# Control.net
KiCad netlist of a schematic drawn in Altium Designer
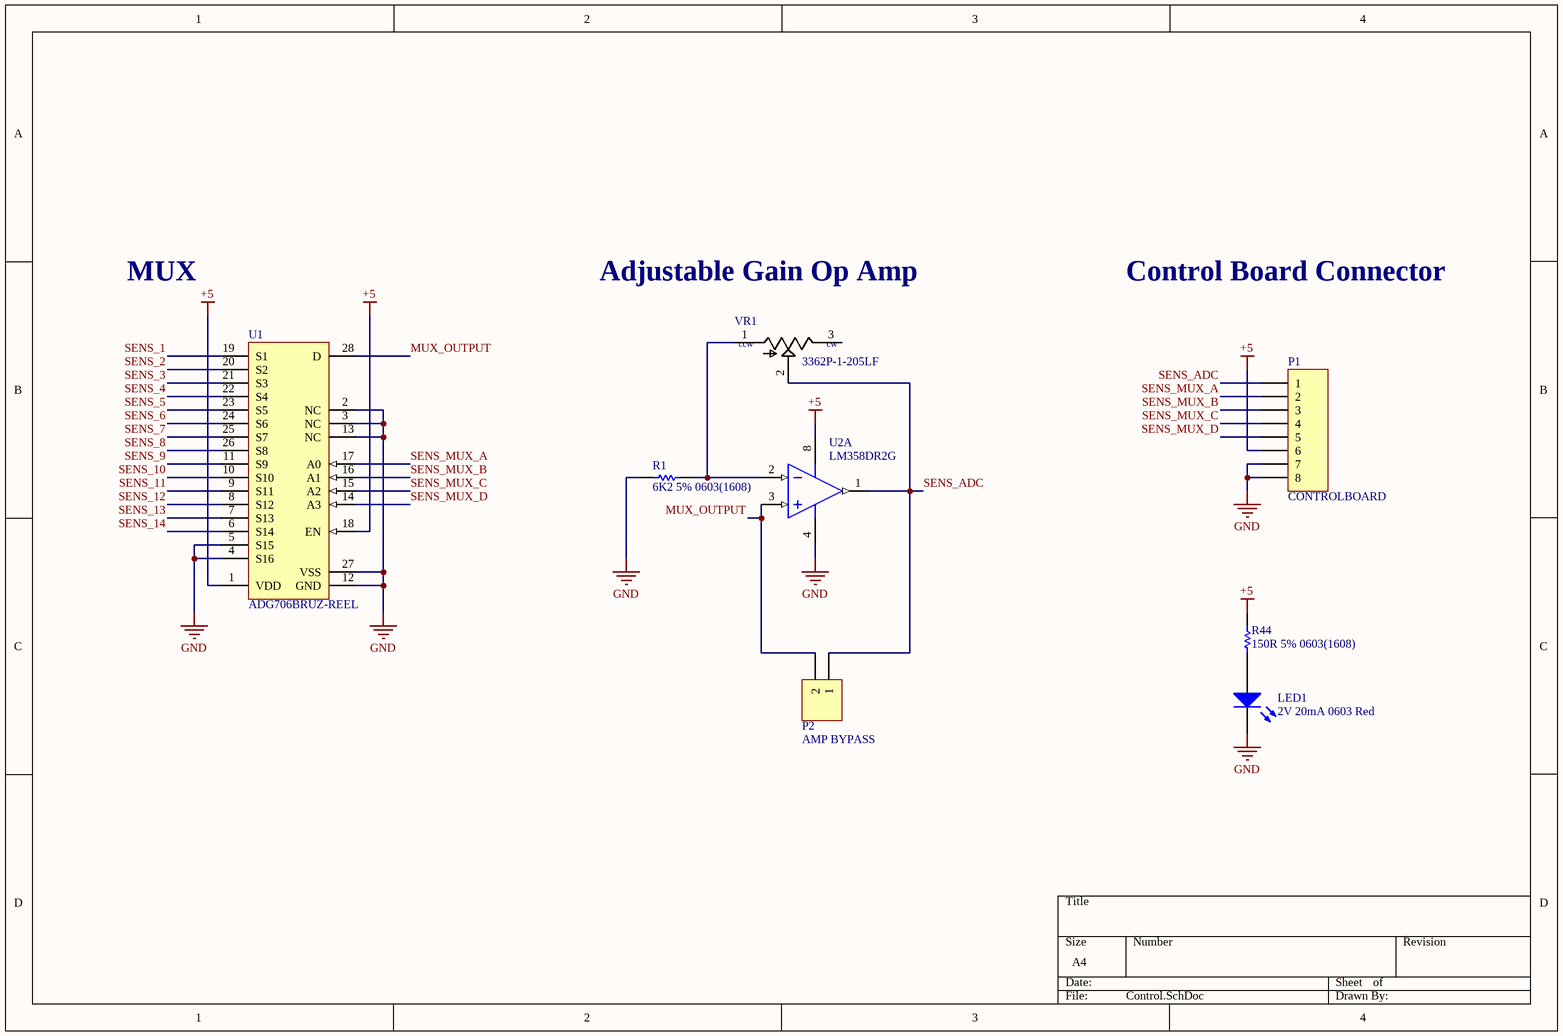
[diagram p0: Control.SchDoc]

(export (version "E")
  (design (tool "Eeschema 10.0.6"))
  (components
    (comp (ref "LED1")
      (value "2V 20mA 0603 Red")
      (footprint "0603_A")
      (description "SMD mono-color Chip LED, WL-SMCW, Red")
      (fields (field (name "MANUFACTURER") "Wuerth Elektronik") (field (name "PARTNUMBER") "150060RS75000"))
      (libsource (lib "Altium Content Vault") (part "WE-LED_K1A2-2"))
    )
    (comp (ref "P1")
      (value "CONTROLBOARD")
      (footprint "HDR1X8")
      (description "Header, 8-Pin")
      (fields (field (name "PUBLISHER") "Altium Limited"))
      (libsource (lib "Miscellaneous Connectors") (part "Header 8"))
    )
    (comp (ref "P2")
      (value "AMP BYPASS")
      (footprint "HDR1X2")
      (description "Header, 2-Pin")
      (fields (field (name "PUBLISHER") "Altium Limited"))
      (libsource (lib "Miscellaneous Connectors") (part "Header 2"))
    )
    (comp (ref "R1")
      (value "6K2 5% 0603(1608)")
      (footprint "RESC0603(1608)_L")
      (description "6K2 0.1W 5% 0603 (1608 Metric)  SMD")
      (fields (field (name "TOLERANCE") "5 %") (field (name "POWER") "0.1 W"))
      (libsource (lib "Altium Content Vault") (part "RES"))
    )
    (comp (ref "R44")
      (value "150R 5% 0603(1608)")
      (footprint "RESC0603(1608)_L")
      (description "150R 0.1W 5% 0603 (1608 Metric)  SMD")
      (fields (field (name "POWER") "0.1 W") (field (name "TOLERANCE") "5 %"))
      (libsource (lib "Altium Content Vault") (part "RES"))
    )
    (comp (ref "U1")
      (value "ADG706BRUZ-REEL")
      (footprint "ADI-RU-28_M")
      (fields (field (name "MANUFACTURER") "Analog Devices"))
      (libsource (lib "Altium Content Vault") (part "ADI-ADG706-RU-28"))
    )
    (comp (ref "U2")
      (value "LM358DR2G")
      (footprint "ONSC-SOIC-8-751-07_V")
      (fields (field (name "MANUFACTURER") "On Semiconductor"))
      (libsource (lib "Altium Content Vault") (part "ONSC-LM358_NCV2904-8"))
    )
    (comp (ref "VR1")
      (value "3362P-1-205LF")
      (footprint "*TRIM_3362P-1-205LF")
      (fields (field (name "MF") "Bourns"))
      (libsource (lib "3362P-1-205LF") (part "3362P-1-205LF"))
    )
  )
  (nets
    (net (code "1") (name "+5") (class "Default")
      (node (ref "P1") (pin "6") (pinfunction "6_6") (pintype "passive"))
      (node (ref "R44") (pin "2") (pinfunction "2_2") (pintype "passive"))
      (node (ref "U1") (pin "1") (pinfunction "VDD_1") (pintype "power_in"))
      (node (ref "U1") (pin "18") (pinfunction "EN_18") (pintype "input"))
      (node (ref "U2") (pin "8") (pinfunction "VCC_8") (pintype "power_in"))
    )
    (net (code "2") (name "/MUX_OUTPUT") (class "Default")
      (node (ref "P2") (pin "2") (pinfunction "2_2") (pintype "passive"))
      (node (ref "U1") (pin "28") (pinfunction "D_28") (pintype "passive"))
      (node (ref "U2") (pin "3") (pinfunction "INA+_3") (pintype "input"))
    )
    (net (code "3") (name "/SENS_1") (class "Default")
      (node (ref "U1") (pin "19") (pinfunction "S1_19") (pintype "passive"))
    )
    (net (code "4") (name "/SENS_2") (class "Default")
      (node (ref "U1") (pin "20") (pinfunction "S2_20") (pintype "passive"))
    )
    (net (code "5") (name "/SENS_3") (class "Default")
      (node (ref "U1") (pin "21") (pinfunction "S3_21") (pintype "passive"))
    )
    (net (code "6") (name "/SENS_4") (class "Default")
      (node (ref "U1") (pin "22") (pinfunction "S4_22") (pintype "passive"))
    )
    (net (code "7") (name "/SENS_5") (class "Default")
      (node (ref "U1") (pin "23") (pinfunction "S5_23") (pintype "passive"))
    )
    (net (code "8") (name "/SENS_6") (class "Default")
      (node (ref "U1") (pin "24") (pinfunction "S6_24") (pintype "passive"))
    )
    (net (code "9") (name "/SENS_7") (class "Default")
      (node (ref "U1") (pin "25") (pinfunction "S7_25") (pintype "passive"))
    )
    (net (code "10") (name "/SENS_8") (class "Default")
      (node (ref "U1") (pin "26") (pinfunction "S8_26") (pintype "passive"))
    )
    (net (code "11") (name "/SENS_9") (class "Default")
      (node (ref "U1") (pin "11") (pinfunction "S9_11") (pintype "passive"))
    )
    (net (code "12") (name "/SENS_10") (class "Default")
      (node (ref "U1") (pin "10") (pinfunction "S10_10") (pintype "passive"))
    )
    (net (code "13") (name "/SENS_11") (class "Default")
      (node (ref "U1") (pin "9") (pinfunction "S11_9") (pintype "passive"))
    )
    (net (code "14") (name "/SENS_12") (class "Default")
      (node (ref "U1") (pin "8") (pinfunction "S12_8") (pintype "passive"))
    )
    (net (code "15") (name "/SENS_13") (class "Default")
      (node (ref "U1") (pin "7") (pinfunction "S13_7") (pintype "passive"))
    )
    (net (code "16") (name "/SENS_14") (class "Default")
      (node (ref "U1") (pin "6") (pinfunction "S14_6") (pintype "passive"))
    )
    (net (code "17") (name "/SENS_ADC") (class "Default")
      (node (ref "P1") (pin "1") (pinfunction "1_1") (pintype "passive"))
      (node (ref "P2") (pin "1") (pinfunction "1_1") (pintype "passive"))
      (node (ref "U2") (pin "1") (pinfunction "OUTA_1") (pintype "output"))
      (node (ref "VR1") (pin "2") (pinfunction "WIPER_2") (pintype "passive"))
    )
    (net (code "18") (name "/SENS_MUX_A") (class "Default")
      (node (ref "P1") (pin "2") (pinfunction "2_2") (pintype "passive"))
      (node (ref "U1") (pin "17") (pinfunction "A0_17") (pintype "input"))
    )
    (net (code "19") (name "/SENS_MUX_B") (class "Default")
      (node (ref "P1") (pin "3") (pinfunction "3_3") (pintype "passive"))
      (node (ref "U1") (pin "16") (pinfunction "A1_16") (pintype "input"))
    )
    (net (code "20") (name "/SENS_MUX_C") (class "Default")
      (node (ref "P1") (pin "4") (pinfunction "4_4") (pintype "passive"))
      (node (ref "U1") (pin "15") (pinfunction "A2_15") (pintype "input"))
    )
    (net (code "21") (name "/SENS_MUX_D") (class "Default")
      (node (ref "P1") (pin "5") (pinfunction "5_5") (pintype "passive"))
      (node (ref "U1") (pin "14") (pinfunction "A3_14") (pintype "input"))
    )
    (net (code "22") (name "GND") (class "Default")
      (node (ref "LED1") (pin "1") (pinfunction "K_1") (pintype "passive"))
      (node (ref "P1") (pin "7") (pinfunction "7_7") (pintype "passive"))
      (node (ref "P1") (pin "8") (pinfunction "8_8") (pintype "passive"))
      (node (ref "R1") (pin "1") (pinfunction "1_1") (pintype "passive"))
      (node (ref "U1") (pin "12") (pinfunction "GND_12") (pintype "power_in"))
      (node (ref "U1") (pin "13") (pinfunction "NC_13") (pintype "passive"))
      (node (ref "U1") (pin "2") (pinfunction "NC_2") (pintype "passive"))
      (node (ref "U1") (pin "27") (pinfunction "VSS_27") (pintype "power_in"))
      (node (ref "U1") (pin "3") (pinfunction "NC_3") (pintype "passive"))
      (node (ref "U1") (pin "4") (pinfunction "S16_4") (pintype "passive"))
      (node (ref "U1") (pin "5") (pinfunction "S15_5") (pintype "passive"))
      (node (ref "U2") (pin "4") (pinfunction "VEE/GND_4") (pintype "power_in"))
    )
    (net (code "23") (name "Net-(LED1-A)") (class "Default")
      (node (ref "LED1") (pin "2") (pinfunction "A_2") (pintype "passive"))
      (node (ref "R44") (pin "1") (pinfunction "1_1") (pintype "passive"))
    )
    (net (code "24") (name "Net-(U2A-INA-)") (class "Default")
      (node (ref "R1") (pin "2") (pinfunction "2_2") (pintype "passive"))
      (node (ref "U2") (pin "2") (pinfunction "INA-_2") (pintype "input"))
      (node (ref "VR1") (pin "1") (pinfunction "CCW_1") (pintype "passive"))
    )
    (net (code "25") (name "unconnected-(VR1-CW-Pad3)") (class "Default")
      (node (ref "VR1") (pin "3") (pinfunction "CW_3") (pintype "passive"))
    )
  )
)
